# QT_Py_SAM_L21.net
KiCad netlist of a schematic drawn in EAGLE
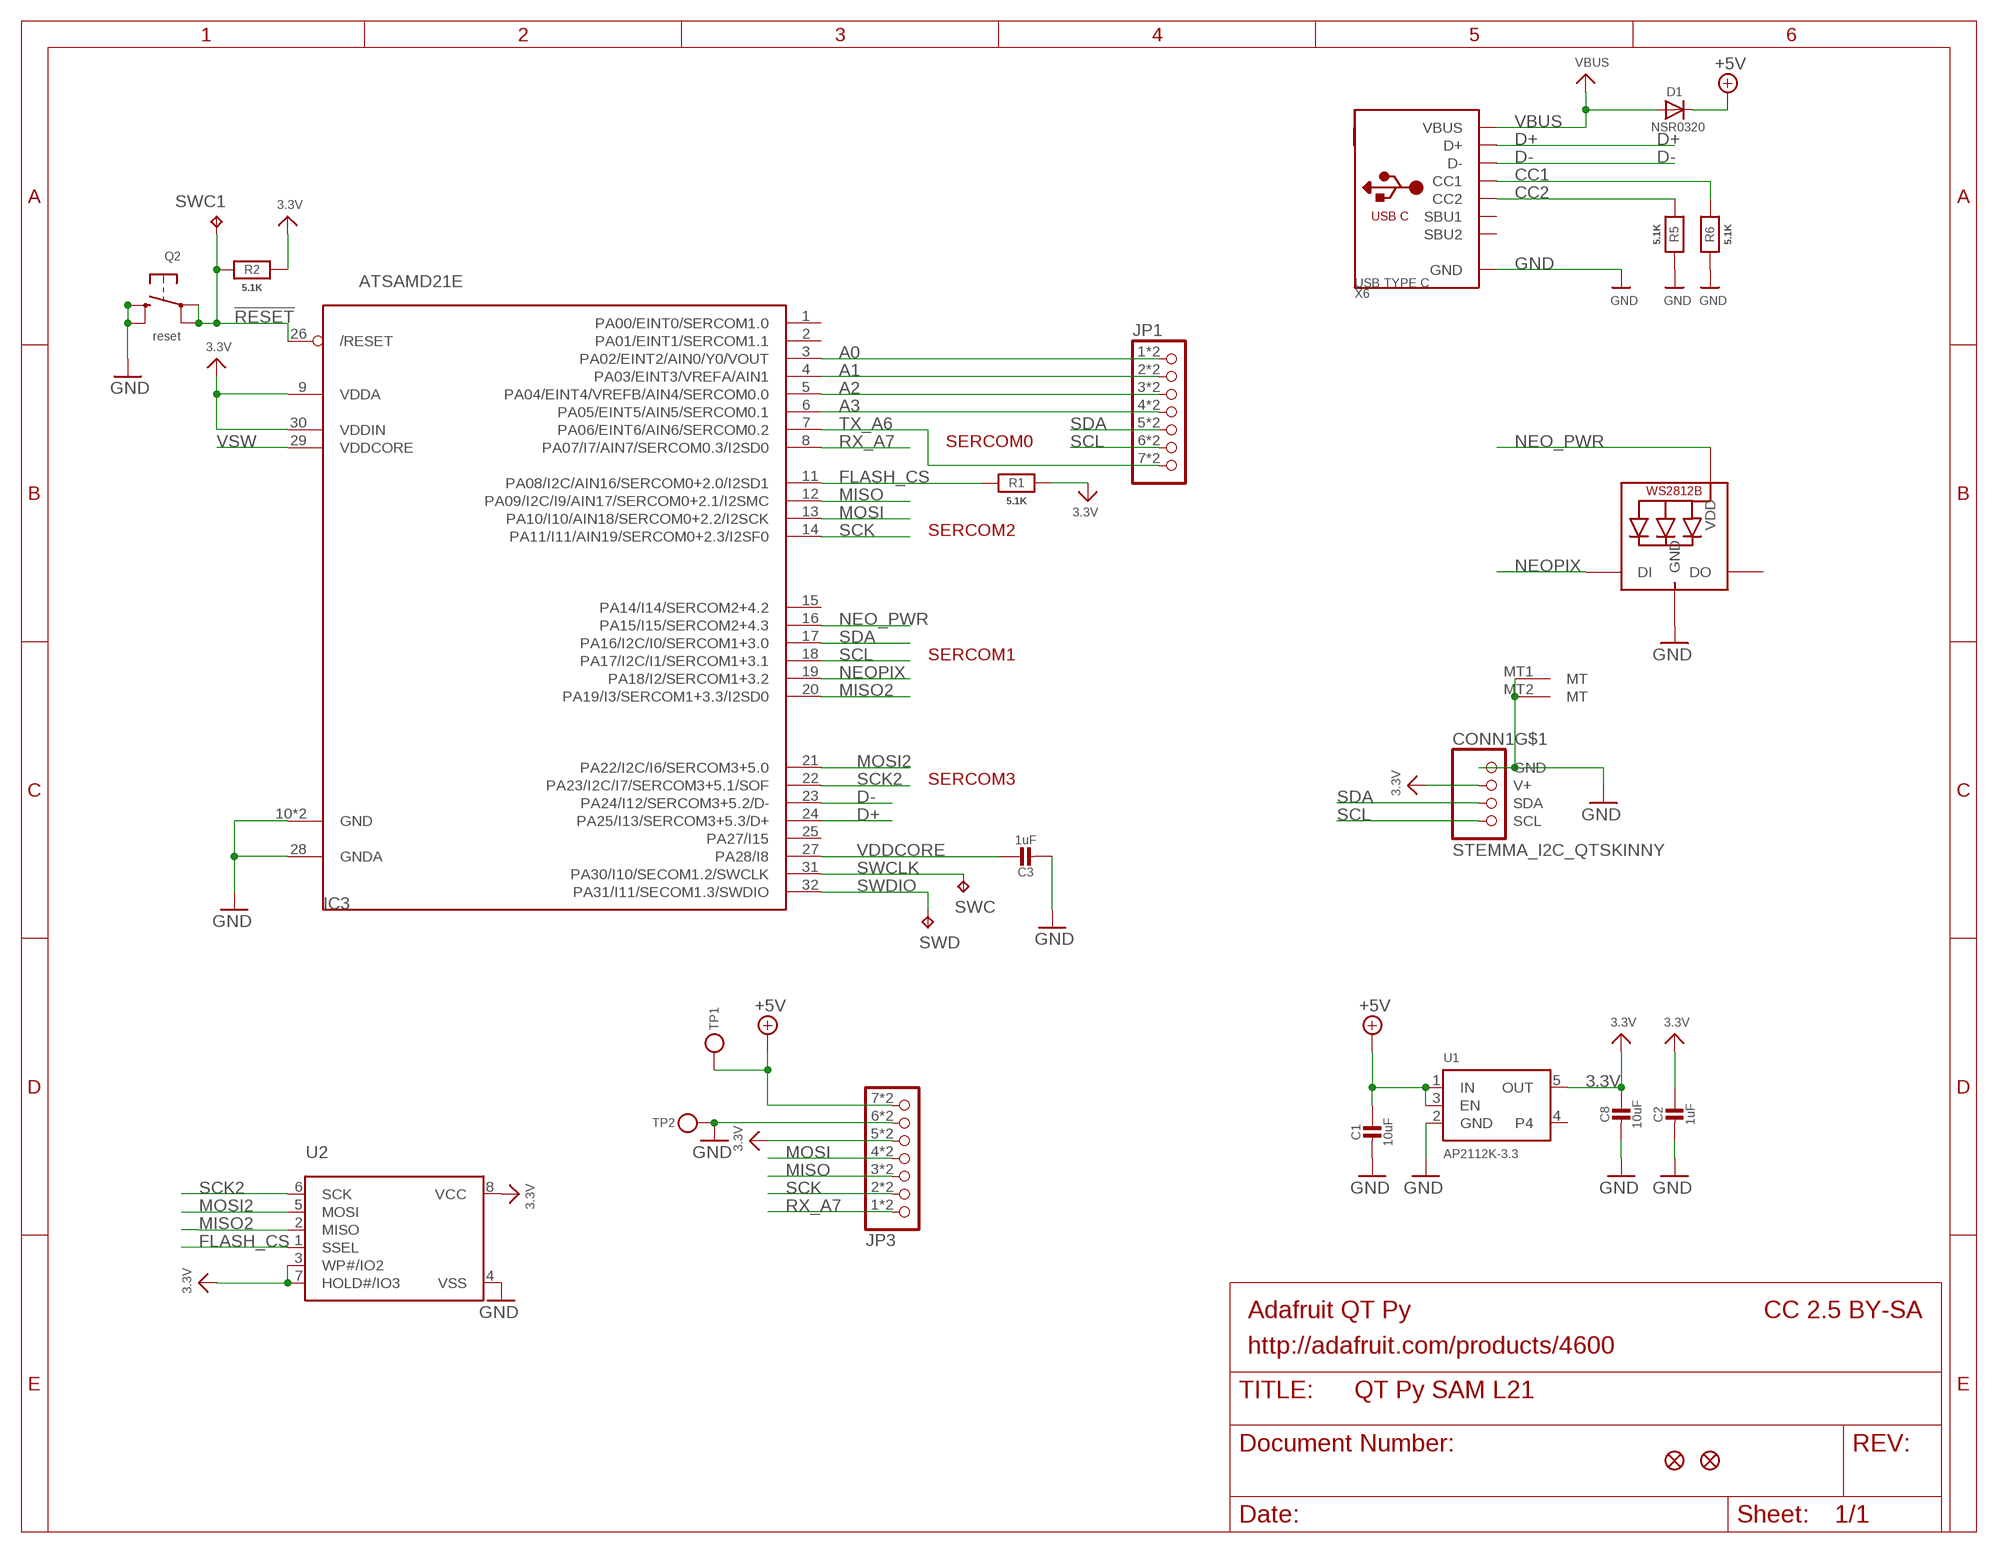
[diagram p0: schematic, sheet 1]

(export (version "E")
  (design (tool "Eeschema 10.0.6"))
  (components
    (comp (ref "C1")
      (value "10uF")
      (footprint "eagle-import:_0805MP")
      (libsource (lib "eagle-import") (part "CAP_CERAMIC_0805MP"))
    )
    (comp (ref "C2")
      (value "1uF")
      (footprint "eagle-import:_0402NO")
      (libsource (lib "eagle-import") (part "CAP_CERAMIC_0402NO"))
    )
    (comp (ref "C3")
      (value "1uF")
      (footprint "eagle-import:_0402NO")
      (libsource (lib "eagle-import") (part "CAP_CERAMIC_0402NO"))
    )
    (comp (ref "C8")
      (value "10uF")
      (footprint "eagle-import:_0805MP")
      (libsource (lib "eagle-import") (part "CAP_CERAMIC_0805MP"))
    )
    (comp (ref "CONN1")
      (value "STEMMA_I2C_QTSKINNY")
      (footprint "eagle-import:JST_SH4_SKINNY")
      (libsource (lib "eagle-import") (part "STEMMA_I2C_QTSKINNY"))
    )
    (comp (ref "D1")
      (value "NSR0320")
      (footprint "eagle-import:SOD-323_MINI")
      (libsource (lib "eagle-import") (part "DIODE_SOD323MINI"))
    )
    (comp (ref "IC3")
      (value "ATSAMD21E")
      (footprint "eagle-import:QFN32_5MM")
      (libsource (lib "eagle-import") (part "ATSAMD21E"))
    )
    (comp (ref "JP1")
      (value "HEADER-1X7_CASTEL")
      (footprint "eagle-import:1X07_CASTEL")
      (libsource (lib "eagle-import") (part "HEADER-1X7_CASTEL"))
    )
    (comp (ref "JP3")
      (value "HEADER-1X7_CASTEL")
      (footprint "eagle-import:1X07_CASTEL")
      (libsource (lib "eagle-import") (part "HEADER-1X7_CASTEL"))
    )
    (comp (ref "LED1")
      (value "WS2812B_SK6805_1515")
      (footprint "eagle-import:SK6805_1515")
      (libsource (lib "eagle-import") (part "WS2812B_SK6805_1515"))
    )
    (comp (ref "Q2")
      (value "reset")
      (footprint "eagle-import:BTN_KMR2_4.6X2.8")
      (libsource (lib "eagle-import") (part "SWITCH_TACT_SMT4.6X2.8"))
    )
    (comp (ref "R1")
      (value "5.1K")
      (footprint "eagle-import:_0402NO")
      (libsource (lib "eagle-import") (part "RESISTOR_0402NO"))
    )
    (comp (ref "R2")
      (value "5.1K")
      (footprint "eagle-import:_0402NO")
      (libsource (lib "eagle-import") (part "RESISTOR_0402NO"))
    )
    (comp (ref "R5")
      (value "5.1K")
      (footprint "eagle-import:_0402NO")
      (libsource (lib "eagle-import") (part "RESISTOR_0402NO"))
    )
    (comp (ref "R6")
      (value "5.1K")
      (footprint "eagle-import:_0402NO")
      (libsource (lib "eagle-import") (part "RESISTOR_0402NO"))
    )
    (comp (ref "SWC")
      (value "TPB1,27")
      (footprint "eagle-import:B1,27")
      (libsource (lib "eagle-import") (part "TPB1,27"))
    )
    (comp (ref "SWC1")
      (value "TPB1,27")
      (footprint "eagle-import:B1,27")
      (libsource (lib "eagle-import") (part "TPB1,27"))
    )
    (comp (ref "SWD")
      (value "TPB1,27")
      (footprint "eagle-import:B1,27")
      (libsource (lib "eagle-import") (part "TPB1,27"))
    )
    (comp (ref "TP1")
      (value "TESTPOINT_1X3")
      (footprint "eagle-import:TESTPOINT_RECT_1X3MM")
      (libsource (lib "eagle-import") (part "TESTPOINT_1X3"))
    )
    (comp (ref "TP2")
      (value "TESTPOINT_1X3")
      (footprint "eagle-import:TESTPOINT_RECT_1X3MM")
      (libsource (lib "eagle-import") (part "TESTPOINT_1X3"))
    )
    (comp (ref "U$6")
      (value "FIDUCIAL_1MM")
      (footprint "eagle-import:FIDUCIAL_1MM")
      (libsource (lib "eagle-import") (part "FIDUCIAL_1MM"))
    )
    (comp (ref "U$8")
      (value "FIDUCIAL_1MM")
      (footprint "eagle-import:FIDUCIAL_1MM")
      (libsource (lib "eagle-import") (part "FIDUCIAL_1MM"))
    )
    (comp (ref "U1")
      (value "AP2112K-3.3")
      (footprint "eagle-import:SOT23-5")
      (libsource (lib "eagle-import") (part "VREG_SOT23-5"))
    )
    (comp (ref "U2")
      (value "SPIFLASH_8PIN")
      (footprint "eagle-import:SOIC8_150MIL")
      (libsource (lib "eagle-import") (part "SPIFLASH_8PIN"))
    )
    (comp (ref "X6")
      (value "USB TYPE C")
      (footprint "eagle-import:USB_C_CUSB31-CFM2AX-01-X")
      (libsource (lib "eagle-import") (part "USB_C"))
    )
  )
  (nets
    (net (code "1") (name "+5V") (class "Default")
      (node (ref "C1") (pin "1") (pinfunction "1_1") (pintype "passive"))
      (node (ref "D1") (pin "C") (pinfunction "C_C") (pintype "passive"))
      (node (ref "JP3") (pin "7") (pinfunction "7_7") (pintype "passive"))
      (node (ref "JP3") (pin "7C") (pinfunction "7_7C") (pintype "passive"))
      (node (ref "TP1") (pin "P$1") (pinfunction "P$1_P$1") (pintype "bidirectional"))
      (node (ref "U1") (pin "1") (pinfunction "IN_1") (pintype "power_in"))
      (node (ref "U1") (pin "3") (pinfunction "EN_3") (pintype "input"))
    )
    (net (code "2") (name "/A0") (class "Default")
      (node (ref "IC3") (pin "3") (pinfunction "PA02/EINT2/AIN0/Y0/VOUT_3") (pintype "bidirectional"))
      (node (ref "JP1") (pin "1") (pinfunction "1_1") (pintype "passive"))
      (node (ref "JP1") (pin "1C") (pinfunction "1_1C") (pintype "passive"))
    )
    (net (code "3") (name "/A1") (class "Default")
      (node (ref "IC3") (pin "4") (pinfunction "PA03/EINT3/VREFA/AIN1_4") (pintype "bidirectional"))
      (node (ref "JP1") (pin "2") (pinfunction "2_2") (pintype "passive"))
      (node (ref "JP1") (pin "2C") (pinfunction "2_2C") (pintype "passive"))
    )
    (net (code "4") (name "/A2") (class "Default")
      (node (ref "IC3") (pin "5") (pinfunction "PA04/EINT4/VREFB/AIN4/SERCOM0.0_5") (pintype "bidirectional"))
      (node (ref "JP1") (pin "3") (pinfunction "3_3") (pintype "passive"))
      (node (ref "JP1") (pin "3C") (pinfunction "3_3C") (pintype "passive"))
    )
    (net (code "5") (name "/A3") (class "Default")
      (node (ref "IC3") (pin "6") (pinfunction "PA05/EINT5/AIN5/SERCOM0.1_6") (pintype "bidirectional"))
      (node (ref "JP1") (pin "4") (pinfunction "4_4") (pintype "passive"))
      (node (ref "JP1") (pin "4C") (pinfunction "4_4C") (pintype "passive"))
    )
    (net (code "6") (name "/CC1") (class "Default")
      (node (ref "R6") (pin "2") (pinfunction "2_2") (pintype "passive"))
      (node (ref "X6") (pin "A5") (pinfunction "CC1_A5") (pintype "bidirectional"))
    )
    (net (code "7") (name "/CC2") (class "Default")
      (node (ref "R5") (pin "2") (pinfunction "2_2") (pintype "passive"))
      (node (ref "X6") (pin "B5") (pinfunction "CC2_B5") (pintype "bidirectional"))
    )
    (net (code "8") (name "/D+") (class "Default")
      (node (ref "IC3") (pin "24") (pinfunction "PA25/I13/SERCOM3+5.3/D+_24") (pintype "bidirectional"))
      (node (ref "X6") (pin "A6") (pinfunction "D+_A6") (pintype "bidirectional"))
      (node (ref "X6") (pin "B6") (pinfunction "D+_B6") (pintype "bidirectional"))
    )
    (net (code "9") (name "/D-") (class "Default")
      (node (ref "IC3") (pin "23") (pinfunction "PA24/I12/SERCOM3+5.2/D-_23") (pintype "bidirectional"))
      (node (ref "X6") (pin "A7") (pinfunction "D-_A7") (pintype "bidirectional"))
      (node (ref "X6") (pin "B7") (pinfunction "D-_B7") (pintype "bidirectional"))
    )
    (net (code "10") (name "/FLASH_CS") (class "Default")
      (node (ref "IC3") (pin "11") (pinfunction "PA08/I2C/AIN16/SERCOM0+2.0/I2SD1_11") (pintype "bidirectional"))
      (node (ref "R1") (pin "2") (pinfunction "2_2") (pintype "passive"))
      (node (ref "U2") (pin "1") (pinfunction "SSEL_1") (pintype "bidirectional"))
    )
    (net (code "11") (name "/MISO") (class "Default")
      (node (ref "IC3") (pin "12") (pinfunction "PA09/I2C/I9/AIN17/SERCOM0+2.1/I2SMC_12") (pintype "bidirectional"))
      (node (ref "JP3") (pin "3") (pinfunction "3_3") (pintype "passive"))
      (node (ref "JP3") (pin "3C") (pinfunction "3_3C") (pintype "passive"))
    )
    (net (code "12") (name "/MISO2") (class "Default")
      (node (ref "IC3") (pin "20") (pinfunction "PA19/I3/SERCOM1+3.3/I2SD0_20") (pintype "bidirectional"))
      (node (ref "U2") (pin "2") (pinfunction "MISO_2") (pintype "bidirectional"))
    )
    (net (code "13") (name "/MOSI") (class "Default")
      (node (ref "IC3") (pin "13") (pinfunction "PA10/I10/AIN18/SERCOM0+2.2/I2SCK_13") (pintype "bidirectional"))
      (node (ref "JP3") (pin "4") (pinfunction "4_4") (pintype "passive"))
      (node (ref "JP3") (pin "4C") (pinfunction "4_4C") (pintype "passive"))
    )
    (net (code "14") (name "/MOSI2") (class "Default")
      (node (ref "IC3") (pin "21") (pinfunction "PA22/I2C/I6/SERCOM3+5.0_21") (pintype "bidirectional"))
      (node (ref "U2") (pin "5") (pinfunction "MOSI_5") (pintype "bidirectional"))
    )
    (net (code "15") (name "/NEOPIX") (class "Default")
      (node (ref "IC3") (pin "19") (pinfunction "PA18/I2/SERCOM1+3.2_19") (pintype "bidirectional"))
      (node (ref "LED1") (pin "1") (pinfunction "DI_1") (pintype "input"))
    )
    (net (code "16") (name "/NEO_PWR") (class "Default")
      (node (ref "IC3") (pin "16") (pinfunction "PA15/I15/SERCOM2+4.3_16") (pintype "bidirectional"))
      (node (ref "LED1") (pin "2") (pinfunction "VDD_2") (pintype "power_in"))
    )
    (net (code "17") (name "/RX_A7") (class "Default")
      (node (ref "IC3") (pin "8") (pinfunction "PA07/I7/AIN7/SERCOM0.3/I2SD0_8") (pintype "bidirectional"))
      (node (ref "JP3") (pin "1") (pinfunction "1_1") (pintype "passive"))
      (node (ref "JP3") (pin "1C") (pinfunction "1_1C") (pintype "passive"))
    )
    (net (code "18") (name "/SCK") (class "Default")
      (node (ref "IC3") (pin "14") (pinfunction "PA11/I11/AIN19/SERCOM0+2.3/I2SF0_14") (pintype "bidirectional"))
      (node (ref "JP3") (pin "2") (pinfunction "2_2") (pintype "passive"))
      (node (ref "JP3") (pin "2C") (pinfunction "2_2C") (pintype "passive"))
    )
    (net (code "19") (name "/SCK2") (class "Default")
      (node (ref "IC3") (pin "22") (pinfunction "PA23/I2C/I7/SERCOM3+5.1/SOF_22") (pintype "bidirectional"))
      (node (ref "U2") (pin "6") (pinfunction "SCK_6") (pintype "bidirectional"))
    )
    (net (code "20") (name "/SCL") (class "Default")
      (node (ref "CONN1") (pin "4") (pinfunction "SCL_4") (pintype "passive"))
      (node (ref "IC3") (pin "18") (pinfunction "PA17/I2C/I1/SERCOM1+3.1_18") (pintype "bidirectional"))
      (node (ref "JP1") (pin "6") (pinfunction "6_6") (pintype "passive"))
      (node (ref "JP1") (pin "6C") (pinfunction "6_6C") (pintype "passive"))
    )
    (net (code "21") (name "/SDA") (class "Default")
      (node (ref "CONN1") (pin "3") (pinfunction "SDA_3") (pintype "passive"))
      (node (ref "IC3") (pin "17") (pinfunction "PA16/I2C/I0/SERCOM1+3.0_17") (pintype "bidirectional"))
      (node (ref "JP1") (pin "5") (pinfunction "5_5") (pintype "passive"))
      (node (ref "JP1") (pin "5C") (pinfunction "5_5C") (pintype "passive"))
    )
    (net (code "22") (name "/SWCLK") (class "Default")
      (node (ref "IC3") (pin "31") (pinfunction "PA30/I10/SECOM1.2/SWCLK_31") (pintype "bidirectional"))
      (node (ref "SWC") (pin "TP") (pinfunction "TP_TP") (pintype "input"))
    )
    (net (code "23") (name "/SWDIO") (class "Default")
      (node (ref "IC3") (pin "32") (pinfunction "PA31/I11/SECOM1.3/SWDIO_32") (pintype "bidirectional"))
      (node (ref "SWD") (pin "TP") (pinfunction "TP_TP") (pintype "input"))
    )
    (net (code "24") (name "/TX_A6") (class "Default")
      (node (ref "IC3") (pin "7") (pinfunction "PA06/EINT6/AIN6/SERCOM0.2_7") (pintype "bidirectional"))
      (node (ref "JP1") (pin "7") (pinfunction "7_7") (pintype "passive"))
      (node (ref "JP1") (pin "7C") (pinfunction "7_7C") (pintype "passive"))
    )
    (net (code "25") (name "/VDDCORE") (class "Default")
      (node (ref "C3") (pin "1") (pinfunction "1_1") (pintype "passive"))
      (node (ref "IC3") (pin "27") (pinfunction "PA28/I8_27") (pintype "bidirectional"))
    )
    (net (code "26") (name "/VSW") (class "Default")
      (node (ref "IC3") (pin "29") (pinfunction "VDDCORE_29") (pintype "power_in"))
    )
    (net (code "27") (name "/~{RESET}") (class "Default")
      (node (ref "IC3") (pin "26") (pinfunction "/RESET_26") (pintype "bidirectional"))
      (node (ref "Q2") (pin "A") (pinfunction "P_A") (pintype "passive"))
      (node (ref "Q2") (pin "A'") (pinfunction "P1_A'") (pintype "passive"))
      (node (ref "R2") (pin "2") (pinfunction "2_2") (pintype "passive"))
      (node (ref "SWC1") (pin "TP") (pinfunction "TP_TP") (pintype "input"))
    )
    (net (code "28") (name "3.3V") (class "Default")
      (node (ref "C2") (pin "1") (pinfunction "1_1") (pintype "passive"))
      (node (ref "C8") (pin "1") (pinfunction "1_1") (pintype "passive"))
      (node (ref "CONN1") (pin "2") (pinfunction "V+_2") (pintype "passive"))
      (node (ref "IC3") (pin "30") (pinfunction "VDDIN_30") (pintype "power_in"))
      (node (ref "IC3") (pin "9") (pinfunction "VDDA_9") (pintype "power_in"))
      (node (ref "JP3") (pin "5") (pinfunction "5_5") (pintype "passive"))
      (node (ref "JP3") (pin "5C") (pinfunction "5_5C") (pintype "passive"))
      (node (ref "R1") (pin "1") (pinfunction "1_1") (pintype "passive"))
      (node (ref "R2") (pin "1") (pinfunction "1_1") (pintype "passive"))
      (node (ref "U1") (pin "5") (pinfunction "OUT_5") (pintype "power_in"))
      (node (ref "U2") (pin "3") (pinfunction "WP#/IO2_3") (pintype "bidirectional"))
      (node (ref "U2") (pin "7") (pinfunction "HOLD#/IO3_7") (pintype "bidirectional"))
      (node (ref "U2") (pin "8") (pinfunction "VCC_8") (pintype "bidirectional"))
    )
    (net (code "29") (name "GND") (class "Default")
      (node (ref "C1") (pin "2") (pinfunction "2_2") (pintype "passive"))
      (node (ref "C2") (pin "2") (pinfunction "2_2") (pintype "passive"))
      (node (ref "C3") (pin "2") (pinfunction "2_2") (pintype "passive"))
      (node (ref "C8") (pin "2") (pinfunction "2_2") (pintype "passive"))
      (node (ref "CONN1") (pin "1") (pinfunction "GND_1") (pintype "passive"))
      (node (ref "CONN1") (pin "MT1") (pinfunction "MT_MT1") (pintype "bidirectional"))
      (node (ref "CONN1") (pin "MT2") (pinfunction "MT_MT2") (pintype "bidirectional"))
      (node (ref "IC3") (pin "10") (pinfunction "GND_10") (pintype "power_in"))
      (node (ref "IC3") (pin "28") (pinfunction "GNDA_28") (pintype "power_in"))
      (node (ref "IC3") (pin "33") (pinfunction "GND_33") (pintype "power_in"))
      (node (ref "JP3") (pin "6") (pinfunction "6_6") (pintype "passive"))
      (node (ref "JP3") (pin "6C") (pinfunction "6_6C") (pintype "passive"))
      (node (ref "LED1") (pin "4") (pinfunction "GND_4") (pintype "power_in"))
      (node (ref "Q2") (pin "B") (pinfunction "S_B") (pintype "passive"))
      (node (ref "Q2") (pin "B'") (pinfunction "S1_B'") (pintype "passive"))
      (node (ref "R5") (pin "1") (pinfunction "1_1") (pintype "passive"))
      (node (ref "R6") (pin "1") (pinfunction "1_1") (pintype "passive"))
      (node (ref "TP2") (pin "P$1") (pinfunction "P$1_P$1") (pintype "bidirectional"))
      (node (ref "U1") (pin "2") (pinfunction "GND_2") (pintype "power_in"))
      (node (ref "U2") (pin "4") (pinfunction "VSS_4") (pintype "bidirectional"))
      (node (ref "X6") (pin "A1B12") (pinfunction "GND_A1B12") (pintype "power_in"))
      (node (ref "X6") (pin "B1A12") (pinfunction "GND_B1A12") (pintype "power_in"))
    )
    (net (code "30") (name "VBUS") (class "Default")
      (node (ref "D1") (pin "A") (pinfunction "A_A") (pintype "passive"))
      (node (ref "X6") (pin "A4B9") (pinfunction "VBUS_A4B9") (pintype "power_in"))
      (node (ref "X6") (pin "B4A9") (pinfunction "VBUS_B4A9") (pintype "power_in"))
    )
    (net (code "31") (name "unconnected-(IC3-PA00{slash}EINT0{slash}SERCOM1.0-Pad1)") (class "Default")
      (node (ref "IC3") (pin "1") (pinfunction "PA00/EINT0/SERCOM1.0_1") (pintype "bidirectional"))
    )
    (net (code "32") (name "unconnected-(IC3-PA01{slash}EINT1{slash}SERCOM1.1-Pad2)") (class "Default")
      (node (ref "IC3") (pin "2") (pinfunction "PA01/EINT1/SERCOM1.1_2") (pintype "bidirectional"))
    )
    (net (code "33") (name "unconnected-(IC3-PA14{slash}I14{slash}SERCOM2+4.2-Pad15)") (class "Default")
      (node (ref "IC3") (pin "15") (pinfunction "PA14/I14/SERCOM2+4.2_15") (pintype "bidirectional"))
    )
    (net (code "34") (name "unconnected-(IC3-PA27{slash}I15-Pad25)") (class "Default")
      (node (ref "IC3") (pin "25") (pinfunction "PA27/I15_25") (pintype "bidirectional"))
    )
    (net (code "35") (name "unconnected-(LED1-DO-Pad3)") (class "Default")
      (node (ref "LED1") (pin "3") (pinfunction "DO_3") (pintype "output"))
    )
    (net (code "36") (name "unconnected-(U1-P4-Pad4)") (class "Default")
      (node (ref "U1") (pin "4") (pinfunction "P4_4") (pintype "bidirectional"))
    )
    (net (code "37") (name "unconnected-(X6-SBU1-PadA8)") (class "Default")
      (node (ref "X6") (pin "A8") (pinfunction "SBU1_A8") (pintype "bidirectional"))
    )
    (net (code "38") (name "unconnected-(X6-SBU2-PadB8)") (class "Default")
      (node (ref "X6") (pin "B8") (pinfunction "SBU2_B8") (pintype "bidirectional"))
    )
  )
)
